# rangefinder_adaptor.net
KiCad netlist of a schematic drawn in EAGLE
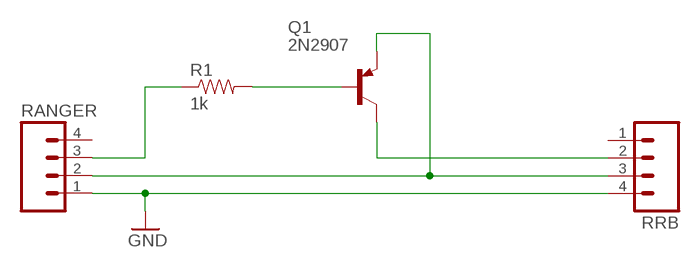
[diagram p0: schematic, sheet 1]

(export (version "E")
  (design (tool "Eeschema 10.0.6"))
  (components
    (comp (ref "Q1")
      (value "2N2907")
      (footprint "eagle-import:TO92-EBC-OVAL")
      (libsource (lib "eagle-import") (part "2N2907"))
    )
    (comp (ref "R1")
      (value "1k")
      (footprint "eagle-import:AXIAL-0.4")
      (libsource (lib "eagle-import") (part "RESISTORPTH-1/4W"))
    )
    (comp (ref "RANGER")
      (value "M04LONGPADS")
      (footprint "eagle-import:1X04_LONGPADS")
      (libsource (lib "eagle-import") (part "M04LONGPADS"))
    )
    (comp (ref "RRB")
      (value "M04LONGPADS")
      (footprint "eagle-import:1X04_LONGPADS")
      (libsource (lib "eagle-import") (part "M04LONGPADS"))
    )
  )
  (nets
    (net (code "1") (name "GND") (class "Default")
      (node (ref "RANGER") (pin "1") (pinfunction "1_1") (pintype "passive"))
      (node (ref "RRB") (pin "4") (pinfunction "4_4") (pintype "passive"))
    )
    (net (code "2") (name "Net-(Q1-PadC)") (class "Default")
      (node (ref "Q1") (pin "C") (pinfunction "C_C") (pintype "passive"))
      (node (ref "RRB") (pin "2") (pinfunction "2_2") (pintype "passive"))
    )
    (net (code "3") (name "Net-(Q1-PadE)") (class "Default")
      (node (ref "Q1") (pin "E") (pinfunction "E_E") (pintype "passive"))
      (node (ref "RANGER") (pin "2") (pinfunction "2_2") (pintype "passive"))
      (node (ref "RRB") (pin "3") (pinfunction "3_3") (pintype "passive"))
    )
    (net (code "4") (name "Net-(R1-1)") (class "Default")
      (node (ref "R1") (pin "P$1") (pinfunction "1_P$1") (pintype "passive"))
      (node (ref "RANGER") (pin "3") (pinfunction "3_3") (pintype "passive"))
    )
    (net (code "5") (name "Net-(R1-2)") (class "Default")
      (node (ref "Q1") (pin "B") (pinfunction "B_B") (pintype "passive"))
      (node (ref "R1") (pin "P$2") (pinfunction "2_P$2") (pintype "passive"))
    )
    (net (code "6") (name "unconnected-(RANGER-Pad4)") (class "Default")
      (node (ref "RANGER") (pin "4") (pinfunction "4_4") (pintype "passive"))
    )
    (net (code "7") (name "unconnected-(RRB-Pad1)") (class "Default")
      (node (ref "RRB") (pin "1") (pinfunction "1_1") (pintype "passive"))
    )
  )
)
